# design.net
KiCad netlist of a schematic drawn in Altium Designer
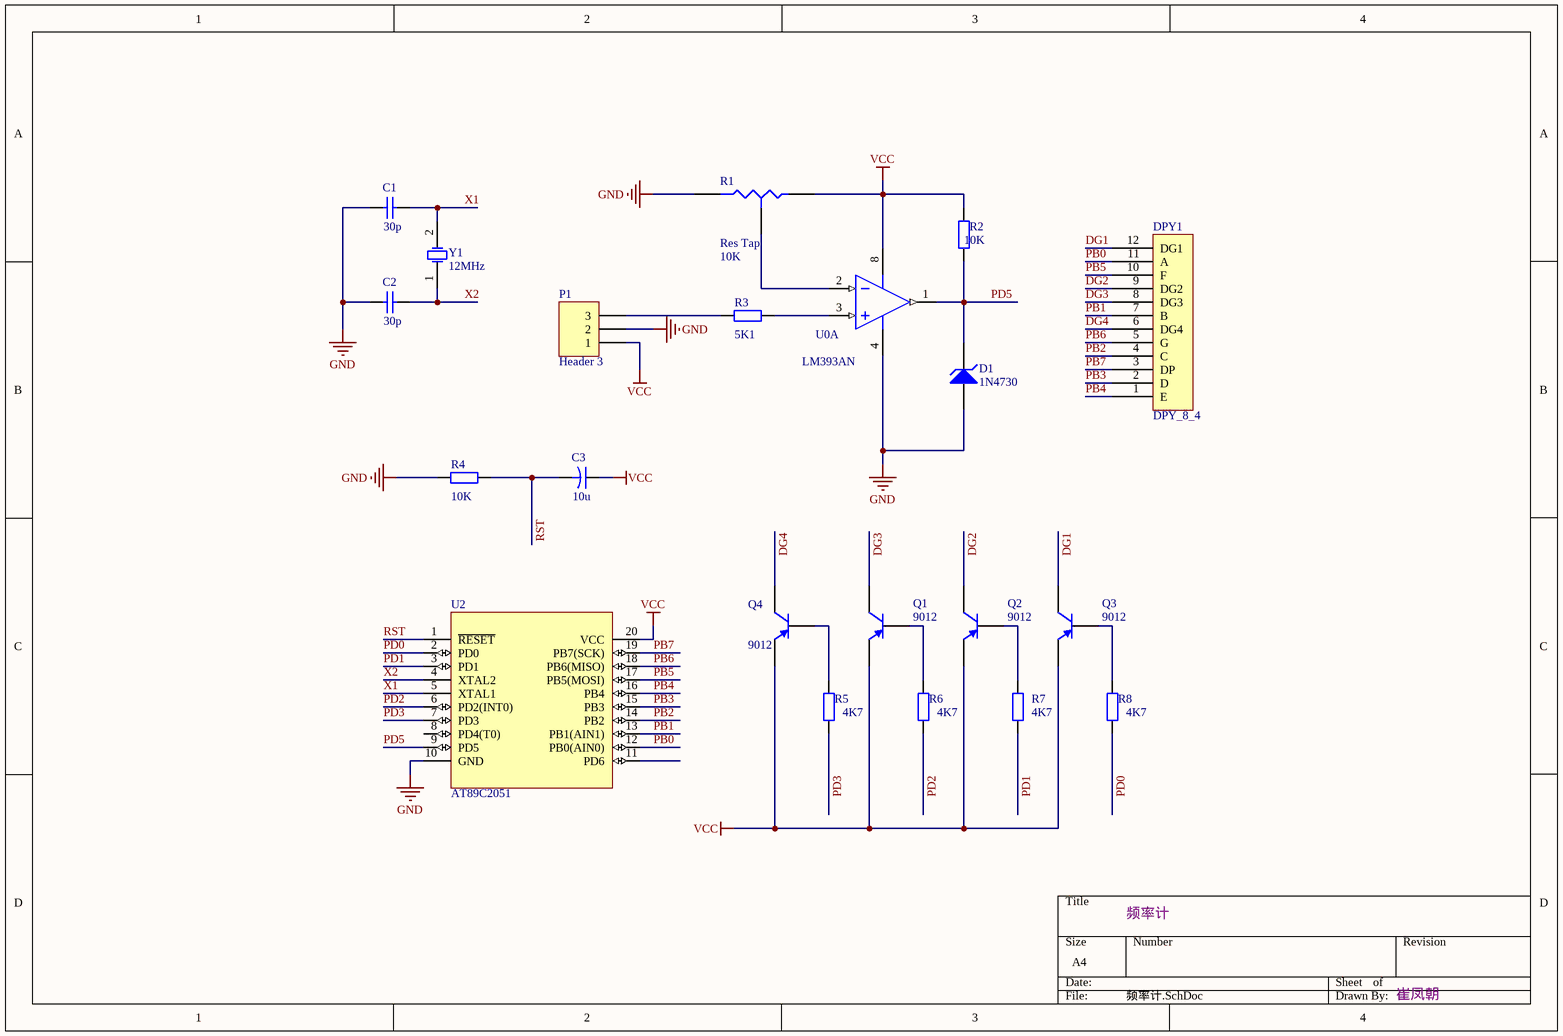
[diagram p0: 频率计.SchDoc]

(export (version "E")
  (design (tool "Eeschema 10.0.6"))
  (components
    (comp (ref "C1")
      (value "30p")
      (footprint "RAD-0.3")
      (description "Capacitor")
      (fields (field (name "Comment") "Cap") (field (name "PUBLISHER") "Altium Limited"))
      (libsource (lib "Miscellaneous Devices") (part "Cap"))
    )
    (comp (ref "C2")
      (value "30p")
      (footprint "RAD-0.3")
      (description "Capacitor")
      (fields (field (name "Comment") "Cap") (field (name "PUBLISHER") "Altium Limited"))
      (libsource (lib "Miscellaneous Devices") (part "Cap"))
    )
    (comp (ref "C3")
      (value "10u")
      (footprint "CAPR5-4X5")
      (description "Capacitor")
      (fields (field (name "Comment") "Cap2") (field (name "PUBLISHER") "Altium Limited"))
      (libsource (lib "Miscellaneous Devices") (part "Cap2"))
    )
    (comp (ref "D1")
      (value "1N4730")
      (footprint "DIODE-0.7")
      (description "Zener Diode")
      (fields (field (name "PUBLISHER") "Altium Limited"))
      (libsource (lib "Miscellaneous Devices") (part "D Zener"))
    )
    (comp (ref "DPY1") (value "DPY_8_4") (footprint "DPY_8_4") (libsource (lib "频率计") (part "DPY_8_4")))
    (comp (ref "P1")
      (value "Header 3")
      (footprint "HDR1X3")
      (description "Header, 3-Pin")
      (fields (field (name "PUBLISHER") "Altium Limited"))
      (libsource (lib "Miscellaneous Connectors") (part "Header 3"))
    )
    (comp (ref "Q1")
      (value "9012")
      (footprint "TO-237-AA")
      (description "PNP Bipolar Transistor")
      (fields (field (name "PUBLISHER") "Altium Limited"))
      (libsource (lib "Miscellaneous Devices") (part "PNP"))
    )
    (comp (ref "Q2")
      (value "9012")
      (footprint "TO-226-AA")
      (description "PNP Bipolar Transistor")
      (fields (field (name "PUBLISHER") "Altium Limited"))
      (libsource (lib "Miscellaneous Devices") (part "PNP"))
    )
    (comp (ref "Q3")
      (value "9012")
      (footprint "TO-226-AA")
      (description "PNP Bipolar Transistor")
      (fields (field (name "PUBLISHER") "Altium Limited"))
      (libsource (lib "Miscellaneous Devices") (part "PNP"))
    )
    (comp (ref "Q4")
      (value "9012")
      (footprint "TO-226-AA")
      (description "PNP Bipolar Transistor")
      (fields (field (name "PUBLISHER") "Altium Limited"))
      (libsource (lib "Miscellaneous Devices") (part "PNP"))
    )
    (comp (ref "R1")
      (value "Res Tap")
      (footprint "VR5")
      (description "Tapped Resistor")
      (fields (field (name "ALTIUM_VALUE") "10K") (field (name "PUBLISHER") "Altium Limited"))
      (libsource (lib "Miscellaneous Devices") (part "Res Tap"))
    )
    (comp (ref "R2")
      (value "10K")
      (footprint "AXIAL-0.4")
      (description "Resistor")
      (fields (field (name "Comment") "Res2") (field (name "PUBLISHER") "Altium Limited"))
      (libsource (lib "Miscellaneous Devices") (part "Res2"))
    )
    (comp (ref "R3")
      (value "5K1")
      (footprint "AXIAL-0.4")
      (description "Resistor")
      (fields (field (name "Comment") "Res2") (field (name "PUBLISHER") "Altium Limited"))
      (libsource (lib "") (part "Res2_1"))
    )
    (comp (ref "R4")
      (value "10K")
      (footprint "AXIAL-0.4")
      (description "Resistor")
      (fields (field (name "Comment") "Res2") (field (name "PUBLISHER") "Altium Limited"))
      (libsource (lib "") (part "Res2_1"))
    )
    (comp (ref "R5")
      (value "4K7")
      (footprint "AXIAL-0.4")
      (description "Resistor")
      (fields (field (name "Comment") "Res2") (field (name "PUBLISHER") "Altium Limited"))
      (libsource (lib "Miscellaneous Devices") (part "Res2"))
    )
    (comp (ref "R6")
      (value "4K7")
      (footprint "AXIAL-0.4")
      (description "Resistor")
      (fields (field (name "Comment") "Res2") (field (name "PUBLISHER") "Altium Limited"))
      (libsource (lib "Miscellaneous Devices") (part "Res2"))
    )
    (comp (ref "R7")
      (value "4K7")
      (footprint "AXIAL-0.4")
      (description "Resistor")
      (fields (field (name "Comment") "Res2") (field (name "PUBLISHER") "Altium Limited"))
      (libsource (lib "Miscellaneous Devices") (part "Res2"))
    )
    (comp (ref "R8")
      (value "4K7")
      (footprint "AXIAL-0.4")
      (description "Resistor")
      (fields (field (name "Comment") "Res2") (field (name "PUBLISHER") "Altium Limited"))
      (libsource (lib "Miscellaneous Devices") (part "Res2"))
    )
    (comp (ref "U0")
      (value "LM393AN")
      (footprint "626-05")
      (description "Dual Comparator")
      (fields (field (name "PUBLISHER") "Altium Limited"))
      (libsource (lib "Motorola Analog Comparator") (part "LM393AN"))
    )
    (comp (ref "U2") (value "AT89C2051") (footprint "DIP20") (libsource (lib "频率计") (part "AT89C2051")))
    (comp (ref "Y1")
      (value "12MHz")
      (footprint "R38")
      (description "Crystal Oscillator")
      (fields (field (name "PUBLISHER") "Altium Limited"))
      (libsource (lib "Miscellaneous Devices") (part "XTAL"))
    )
  )
  (nets
    (net (code "1") (name "/DG1") (class "Default")
      (node (ref "DPY1") (pin "12") (pinfunction "DG1_12") (pintype "passive"))
      (node (ref "Q3") (pin "1") (pinfunction "C_1") (pintype "passive"))
    )
    (net (code "2") (name "/DG2") (class "Default")
      (node (ref "DPY1") (pin "9") (pinfunction "DG2_9") (pintype "passive"))
      (node (ref "Q2") (pin "1") (pinfunction "C_1") (pintype "passive"))
    )
    (net (code "3") (name "/DG3") (class "Default")
      (node (ref "DPY1") (pin "8") (pinfunction "DG3_8") (pintype "passive"))
      (node (ref "Q1") (pin "1") (pinfunction "C_1") (pintype "passive"))
    )
    (net (code "4") (name "/DG4") (class "Default")
      (node (ref "DPY1") (pin "6") (pinfunction "DG4_6") (pintype "passive"))
      (node (ref "Q4") (pin "1") (pinfunction "C_1") (pintype "passive"))
    )
    (net (code "5") (name "/PB0") (class "Default")
      (node (ref "DPY1") (pin "11") (pinfunction "A_11") (pintype "passive"))
      (node (ref "U2") (pin "12") (pinfunction "PB0(AIN0)_12") (pintype "bidirectional"))
    )
    (net (code "6") (name "/PB1") (class "Default")
      (node (ref "DPY1") (pin "7") (pinfunction "B_7") (pintype "passive"))
      (node (ref "U2") (pin "13") (pinfunction "PB1(AIN1)_13") (pintype "bidirectional"))
    )
    (net (code "7") (name "/PB2") (class "Default")
      (node (ref "DPY1") (pin "4") (pinfunction "C_4") (pintype "passive"))
      (node (ref "U2") (pin "14") (pinfunction "PB2_14") (pintype "bidirectional"))
    )
    (net (code "8") (name "/PB3") (class "Default")
      (node (ref "DPY1") (pin "2") (pinfunction "D_2") (pintype "passive"))
      (node (ref "U2") (pin "15") (pinfunction "PB3_15") (pintype "bidirectional"))
    )
    (net (code "9") (name "/PB4") (class "Default")
      (node (ref "DPY1") (pin "1") (pinfunction "E_1") (pintype "passive"))
      (node (ref "U2") (pin "16") (pinfunction "PB4_16") (pintype "bidirectional"))
    )
    (net (code "10") (name "/PB5") (class "Default")
      (node (ref "DPY1") (pin "10") (pinfunction "F_10") (pintype "passive"))
      (node (ref "U2") (pin "17") (pinfunction "PB5(MOSI)_17") (pintype "bidirectional"))
    )
    (net (code "11") (name "/PB6") (class "Default")
      (node (ref "DPY1") (pin "5") (pinfunction "G_5") (pintype "passive"))
      (node (ref "U2") (pin "18") (pinfunction "PB6(MISO)_18") (pintype "bidirectional"))
    )
    (net (code "12") (name "/PB7") (class "Default")
      (node (ref "DPY1") (pin "3") (pinfunction "DP_3") (pintype "passive"))
      (node (ref "U2") (pin "19") (pinfunction "PB7(SCK)_19") (pintype "bidirectional"))
    )
    (net (code "13") (name "/PD0") (class "Default")
      (node (ref "R8") (pin "1") (pinfunction "1_1") (pintype "passive"))
      (node (ref "U2") (pin "2") (pinfunction "PD0_2") (pintype "bidirectional"))
    )
    (net (code "14") (name "/PD1") (class "Default")
      (node (ref "R7") (pin "1") (pinfunction "1_1") (pintype "passive"))
      (node (ref "U2") (pin "3") (pinfunction "PD1_3") (pintype "bidirectional"))
    )
    (net (code "15") (name "/PD2") (class "Default")
      (node (ref "R6") (pin "1") (pinfunction "1_1") (pintype "passive"))
      (node (ref "U2") (pin "6") (pinfunction "PD2(INT0)_6") (pintype "bidirectional"))
    )
    (net (code "16") (name "/PD3") (class "Default")
      (node (ref "R5") (pin "1") (pinfunction "1_1") (pintype "passive"))
      (node (ref "U2") (pin "7") (pinfunction "PD3_7") (pintype "bidirectional"))
    )
    (net (code "17") (name "/PD5") (class "Default")
      (node (ref "D1") (pin "2") (pinfunction "K_2") (pintype "passive"))
      (node (ref "R2") (pin "1") (pinfunction "1_1") (pintype "passive"))
      (node (ref "U0") (pin "1") (pinfunction "OUT_1") (pintype "output"))
      (node (ref "U2") (pin "9") (pinfunction "PD5_9") (pintype "bidirectional"))
    )
    (net (code "18") (name "/RST") (class "Default")
      (node (ref "C3") (pin "2") (pinfunction "2_2") (pintype "passive"))
      (node (ref "R4") (pin "1") (pinfunction "1_1") (pintype "passive"))
      (node (ref "U2") (pin "1") (pinfunction "~{RESET}_1") (pintype "passive"))
    )
    (net (code "19") (name "/X1") (class "Default")
      (node (ref "C1") (pin "2") (pinfunction "2_2") (pintype "passive"))
      (node (ref "U2") (pin "5") (pinfunction "XTAL1_5") (pintype "open_collector"))
      (node (ref "Y1") (pin "2") (pinfunction "OSC2_2") (pintype "passive"))
    )
    (net (code "20") (name "/X2") (class "Default")
      (node (ref "C2") (pin "2") (pinfunction "2_2") (pintype "passive"))
      (node (ref "U2") (pin "4") (pinfunction "XTAL2_4") (pintype "open_collector"))
      (node (ref "Y1") (pin "1") (pinfunction "OSC1_1") (pintype "passive"))
    )
    (net (code "23") (name "GND") (class "Default")
      (node (ref "C1") (pin "1") (pinfunction "1_1") (pintype "passive"))
      (node (ref "C2") (pin "1") (pinfunction "1_1") (pintype "passive"))
      (node (ref "D1") (pin "1") (pinfunction "A_1") (pintype "passive"))
      (node (ref "P1") (pin "2") (pinfunction "2_2") (pintype "passive"))
      (node (ref "R1") (pin "2") (pinfunction "B_2") (pintype "passive"))
      (node (ref "R4") (pin "2") (pinfunction "2_2") (pintype "passive"))
      (node (ref "U0") (pin "4") (pinfunction "GND_4") (pintype "power_in"))
      (node (ref "U2") (pin "10") (pinfunction "GND_10") (pintype "power_in"))
    )
    (net (code "24") (name "Net-(P1-Pad3)") (class "Default")
      (node (ref "P1") (pin "3") (pinfunction "3_3") (pintype "passive"))
      (node (ref "R3") (pin "2") (pinfunction "2_2") (pintype "passive"))
    )
    (net (code "25") (name "Net-(Q1-B)") (class "Default")
      (node (ref "Q1") (pin "2") (pinfunction "B_2") (pintype "passive"))
      (node (ref "R6") (pin "2") (pinfunction "2_2") (pintype "passive"))
    )
    (net (code "26") (name "Net-(Q2-B)") (class "Default")
      (node (ref "Q2") (pin "2") (pinfunction "B_2") (pintype "passive"))
      (node (ref "R7") (pin "2") (pinfunction "2_2") (pintype "passive"))
    )
    (net (code "27") (name "Net-(Q3-B)") (class "Default")
      (node (ref "Q3") (pin "2") (pinfunction "B_2") (pintype "passive"))
      (node (ref "R8") (pin "2") (pinfunction "2_2") (pintype "passive"))
    )
    (net (code "28") (name "Net-(Q4-B)") (class "Default")
      (node (ref "Q4") (pin "2") (pinfunction "B_2") (pintype "passive"))
      (node (ref "R5") (pin "2") (pinfunction "2_2") (pintype "passive"))
    )
    (net (code "29") (name "Net-(R1-TAP)") (class "Default")
      (node (ref "R1") (pin "3") (pinfunction "TAP_3") (pintype "passive"))
      (node (ref "U0") (pin "2") (pinfunction "IN-_2") (pintype "input"))
    )
    (net (code "30") (name "Net-(U0A-IN+)") (class "Default")
      (node (ref "R3") (pin "1") (pinfunction "1_1") (pintype "passive"))
      (node (ref "U0") (pin "3") (pinfunction "IN+_3") (pintype "input"))
    )
    (net (code "31") (name "VCC") (class "Default")
      (node (ref "C3") (pin "1") (pinfunction "1_1") (pintype "passive"))
      (node (ref "P1") (pin "1") (pinfunction "1_1") (pintype "passive"))
      (node (ref "Q1") (pin "3") (pinfunction "E_3") (pintype "passive"))
      (node (ref "Q2") (pin "3") (pinfunction "E_3") (pintype "passive"))
      (node (ref "Q3") (pin "3") (pinfunction "E_3") (pintype "passive"))
      (node (ref "Q4") (pin "3") (pinfunction "E_3") (pintype "passive"))
      (node (ref "R1") (pin "1") (pinfunction "A_1") (pintype "passive"))
      (node (ref "R2") (pin "2") (pinfunction "2_2") (pintype "passive"))
      (node (ref "U0") (pin "8") (pinfunction "V+_8") (pintype "power_in"))
      (node (ref "U2") (pin "20") (pinfunction "VCC_20") (pintype "power_in"))
    )
    (net (code "32") (name "unconnected-(U2-PD4(T0)-Pad8)") (class "Default")
      (node (ref "U2") (pin "8") (pinfunction "PD4(T0)_8") (pintype "bidirectional"))
    )
    (net (code "33") (name "unconnected-(U2-PD6-Pad11)") (class "Default")
      (node (ref "U2") (pin "11") (pinfunction "PD6_11") (pintype "bidirectional"))
    )
  )
)
